# HV_powerSupply_board_20210802.net
KiCad netlist of a schematic drawn in EAGLE
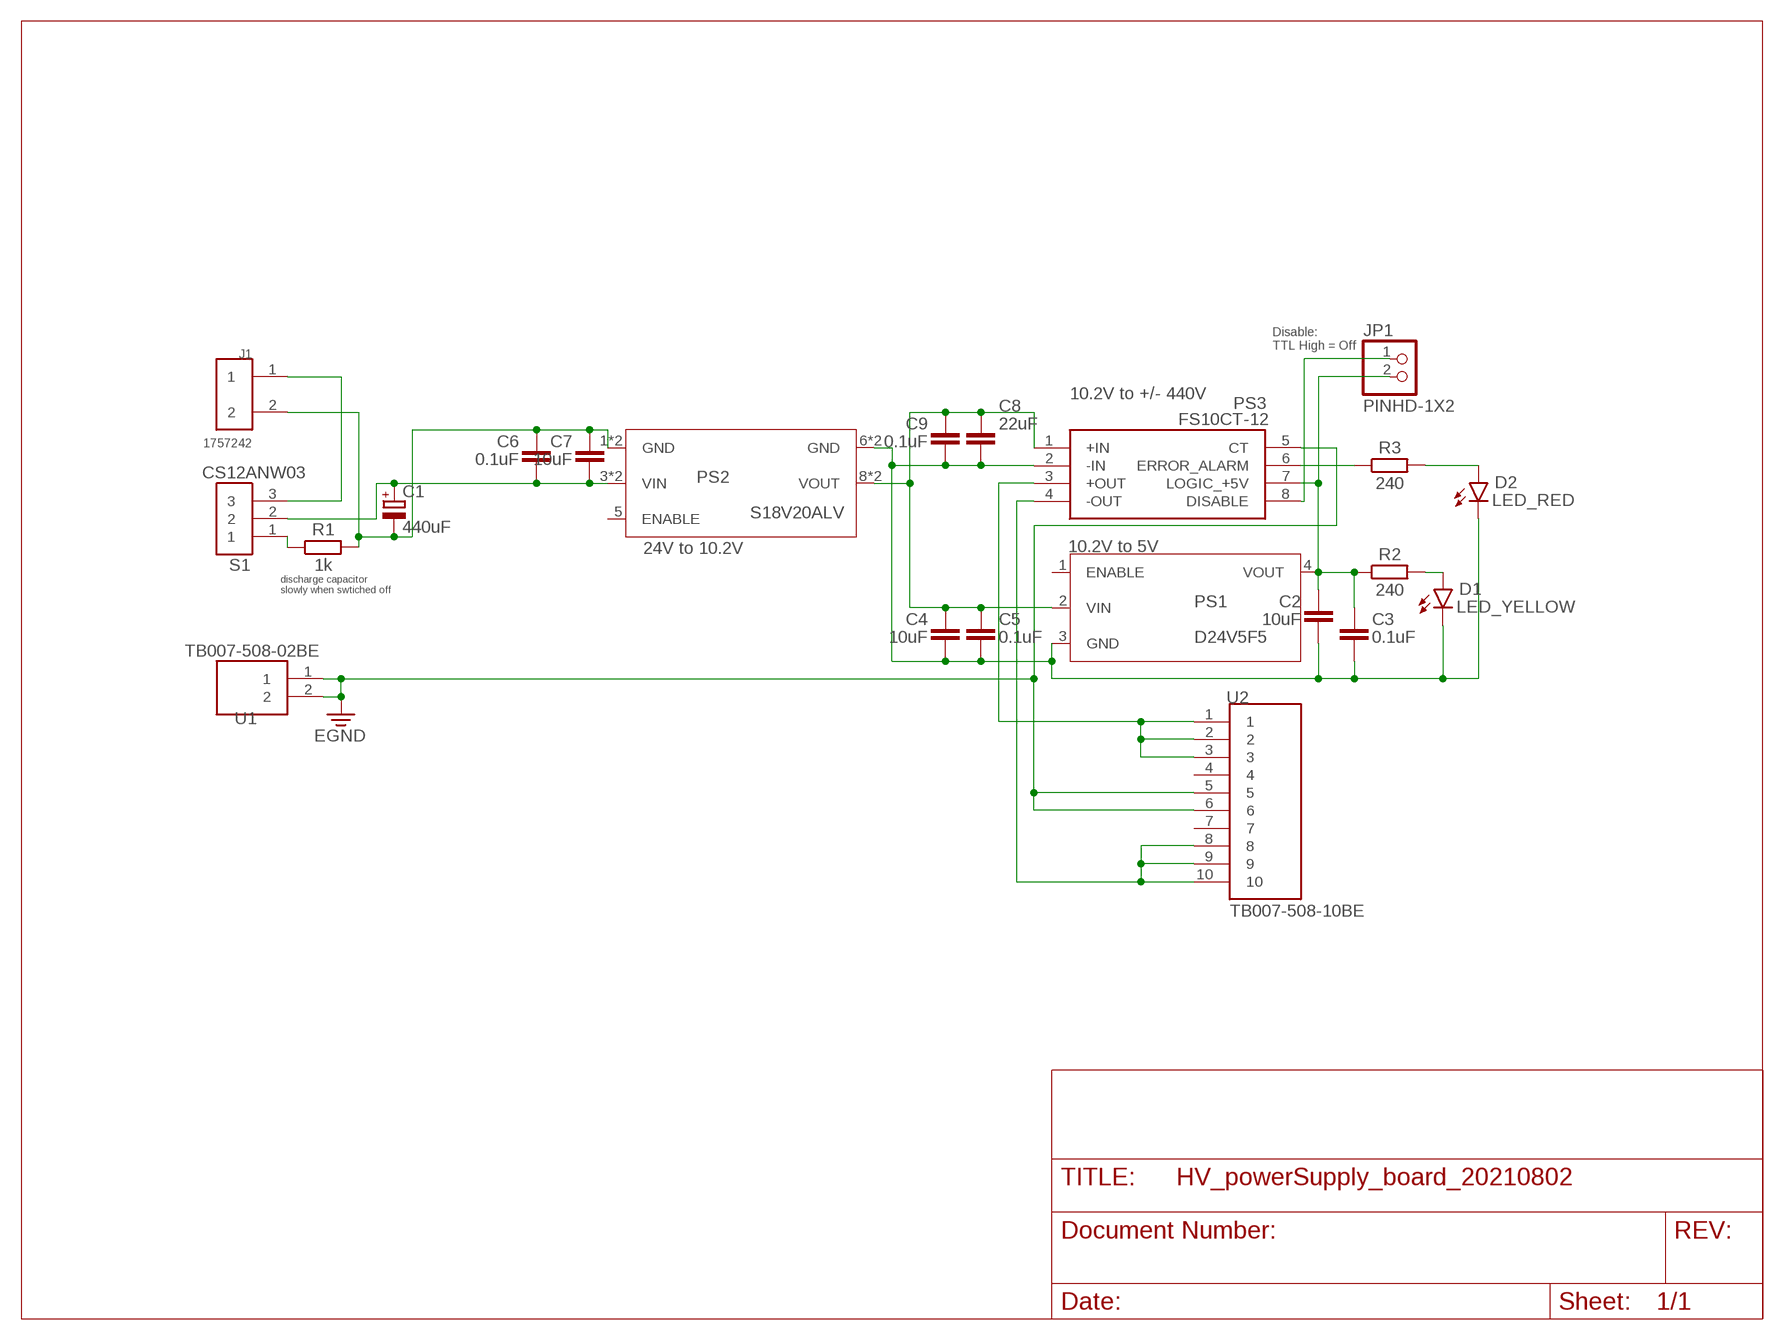
[diagram p0: schematic, sheet 1]

(export (version "E")
  (design (tool "Eeschema 10.0.6"))
  (components
    (comp (ref "C1")
      (value "440uF")
      (footprint "eagle-import:CAPPRD508W65D1000H1100B")
      (libsource (lib "eagle-import") (part "C-POLRADIAL-11MM-DIA_"))
    )
    (comp (ref "C2")
      (value "10uF")
      (footprint "eagle-import:CAPC3225X135")
      (libsource (lib "eagle-import") (part "CCHIP-1210(3225-METRIC)_"))
    )
    (comp (ref "C3")
      (value "0.1uF")
      (footprint "eagle-import:CAPC1608X85")
      (libsource (lib "eagle-import") (part "CCHIP-0603(1608-METRIC)_"))
    )
    (comp (ref "C4")
      (value "10uF")
      (footprint "eagle-import:CAPC3225X135")
      (libsource (lib "eagle-import") (part "CCHIP-1210(3225-METRIC)_"))
    )
    (comp (ref "C5")
      (value "0.1uF")
      (footprint "eagle-import:CAPC1608X85")
      (libsource (lib "eagle-import") (part "CCHIP-0603(1608-METRIC)_"))
    )
    (comp (ref "C6")
      (value "0.1uF")
      (footprint "eagle-import:CAPC1608X85")
      (libsource (lib "eagle-import") (part "CCHIP-0603(1608-METRIC)_"))
    )
    (comp (ref "C7")
      (value "10uF")
      (footprint "eagle-import:CAPC3225X135")
      (libsource (lib "eagle-import") (part "CCHIP-1210(3225-METRIC)_"))
    )
    (comp (ref "C8")
      (value "22uF")
      (footprint "eagle-import:CAPC3225X135")
      (libsource (lib "eagle-import") (part "CCHIP-1210(3225-METRIC)_"))
    )
    (comp (ref "C9")
      (value "0.1uF")
      (footprint "eagle-import:CAPC1608X85")
      (libsource (lib "eagle-import") (part "CCHIP-0603(1608-METRIC)_"))
    )
    (comp (ref "D1")
      (value "LED_YELLOW")
      (footprint "eagle-import:LEDRD254W60D565H860B_Y")
      (libsource (lib "eagle-import") (part "LED_RADIALYELLOW_"))
    )
    (comp (ref "D2")
      (value "LED_RED")
      (footprint "eagle-import:LEDRD254W60D565H860B")
      (libsource (lib "eagle-import") (part "LED_RADIALRED_"))
    )
    (comp (ref "J1")
      (value "1757242")
      (footprint "eagle-import:PHOENIX_1757242")
      (fields (field (name "DIGI-KEY_PART_NUMBER") "277-1106-ND") (field (name "MF") "Phoenix Contact"))
      (libsource (lib "eagle-import") (part "1757242"))
    )
    (comp (ref "JP1")
      (value "PINHD-1X2")
      (footprint "eagle-import:1X02")
      (libsource (lib "eagle-import") (part "PINHD-1X2"))
    )
    (comp (ref "PS1")
      (value "D24V5F5")
      (footprint "eagle-import:D24V5F5")
      (libsource (lib "eagle-import") (part "D24V5F5"))
    )
    (comp (ref "PS2")
      (value "S18V20ALV")
      (footprint "eagle-import:S18V20ALV")
      (libsource (lib "eagle-import") (part "S18V20ALV"))
    )
    (comp (ref "PS3")
      (value "FS10CT-12")
      (footprint "eagle-import:FS10CT12")
      (libsource (lib "eagle-import") (part "FS10CT-12"))
    )
    (comp (ref "R1")
      (value "1k")
      (footprint "eagle-import:RESC3216X70")
      (libsource (lib "eagle-import") (part "RCHIP-1206(3216-METRIC)_"))
    )
    (comp (ref "R2")
      (value "240")
      (footprint "eagle-import:RESC3216X70")
      (libsource (lib "eagle-import") (part "RCHIP-1206(3216-METRIC)_"))
    )
    (comp (ref "R3")
      (value "240")
      (footprint "eagle-import:RESC3216X70")
      (libsource (lib "eagle-import") (part "RCHIP-1206(3216-METRIC)_"))
    )
    (comp (ref "S1")
      (value "CS12ANW03")
      (footprint "eagle-import:CS12ANW03")
      (fields (field (name "MOUSER_PART_NUMBER") "633-CS12ANW03"))
      (libsource (lib "eagle-import") (part "CS12ANW03"))
    )
    (comp (ref "U1")
      (value "TB007-508-02BE")
      (footprint "eagle-import:CUI_TB007-508-02BE")
      (fields (field (name "DIGI-KEY_PART_NUMBER") "102-6203-ND") (field (name "MF") "CUI Devices"))
      (libsource (lib "eagle-import") (part "TB007-508-02BE"))
    )
    (comp (ref "U2")
      (value "TB007-508-10BE")
      (footprint "eagle-import:CUI_TB007-508-10BE")
      (fields (field (name "MANUFACTURER") "CUI"))
      (libsource (lib "eagle-import") (part "TB007-508-10BE"))
    )
  )
  (nets
    (net (code "1") (name "EGND") (class "Default")
      (node (ref "PS3") (pin "5") (pinfunction "CT_5") (pintype "bidirectional"))
      (node (ref "U1") (pin "1") (pinfunction "1_1") (pintype "passive"))
      (node (ref "U1") (pin "2") (pinfunction "2_2") (pintype "passive"))
      (node (ref "U2") (pin "5") (pinfunction "5_5") (pintype "passive"))
      (node (ref "U2") (pin "6") (pinfunction "6_6") (pintype "passive"))
    )
    (net (code "2") (name "Net-(C1-+)") (class "Default")
      (node (ref "C1") (pin "1") (pinfunction "+_1") (pintype "passive"))
      (node (ref "C6") (pin "2") (pinfunction "2_2") (pintype "passive"))
      (node (ref "C7") (pin "2") (pinfunction "2_2") (pintype "passive"))
      (node (ref "PS2") (pin "3") (pinfunction "VIN_3") (pintype "bidirectional"))
      (node (ref "PS2") (pin "4") (pinfunction "VIN_4") (pintype "bidirectional"))
      (node (ref "S1") (pin "2") (pinfunction "2_2") (pintype "bidirectional"))
    )
    (net (code "3") (name "Net-(C1--)") (class "Default")
      (node (ref "C1") (pin "2") (pinfunction "-_2") (pintype "passive"))
      (node (ref "C6") (pin "1") (pinfunction "1_1") (pintype "passive"))
      (node (ref "C7") (pin "1") (pinfunction "1_1") (pintype "passive"))
      (node (ref "J1") (pin "2") (pinfunction "2_2") (pintype "passive"))
      (node (ref "PS2") (pin "1") (pinfunction "GND_1") (pintype "bidirectional"))
      (node (ref "PS2") (pin "2") (pinfunction "GND_2") (pintype "bidirectional"))
      (node (ref "R1") (pin "2") (pinfunction "2_2") (pintype "passive"))
    )
    (net (code "4") (name "Net-(D1-A)") (class "Default")
      (node (ref "D1") (pin "1") (pinfunction "A_1") (pintype "passive"))
      (node (ref "R2") (pin "2") (pinfunction "2_2") (pintype "passive"))
    )
    (net (code "5") (name "Net-(D1-C)") (class "Default")
      (node (ref "C2") (pin "2") (pinfunction "2_2") (pintype "passive"))
      (node (ref "C3") (pin "2") (pinfunction "2_2") (pintype "passive"))
      (node (ref "C4") (pin "2") (pinfunction "2_2") (pintype "passive"))
      (node (ref "C5") (pin "2") (pinfunction "2_2") (pintype "passive"))
      (node (ref "C8") (pin "2") (pinfunction "2_2") (pintype "passive"))
      (node (ref "C9") (pin "2") (pinfunction "2_2") (pintype "passive"))
      (node (ref "D1") (pin "2") (pinfunction "C_2") (pintype "passive"))
      (node (ref "D2") (pin "2") (pinfunction "C_2") (pintype "passive"))
      (node (ref "PS1") (pin "3") (pinfunction "GND_3") (pintype "bidirectional"))
      (node (ref "PS2") (pin "6") (pinfunction "GND_6") (pintype "bidirectional"))
      (node (ref "PS2") (pin "7") (pinfunction "GND_7") (pintype "bidirectional"))
      (node (ref "PS3") (pin "2") (pinfunction "-IN_2") (pintype "bidirectional"))
    )
    (net (code "6") (name "Net-(D2-A)") (class "Default")
      (node (ref "D2") (pin "1") (pinfunction "A_1") (pintype "passive"))
      (node (ref "R3") (pin "2") (pinfunction "2_2") (pintype "passive"))
    )
    (net (code "7") (name "Net-(J1-Pad1)") (class "Default")
      (node (ref "J1") (pin "1") (pinfunction "1_1") (pintype "passive"))
      (node (ref "S1") (pin "3") (pinfunction "3_3") (pintype "bidirectional"))
    )
    (net (code "8") (name "Net-(PS1-VIN)") (class "Default")
      (node (ref "C4") (pin "1") (pinfunction "1_1") (pintype "passive"))
      (node (ref "C5") (pin "1") (pinfunction "1_1") (pintype "passive"))
      (node (ref "C8") (pin "1") (pinfunction "1_1") (pintype "passive"))
      (node (ref "C9") (pin "1") (pinfunction "1_1") (pintype "passive"))
      (node (ref "PS1") (pin "2") (pinfunction "VIN_2") (pintype "bidirectional"))
      (node (ref "PS2") (pin "8") (pinfunction "VOUT_8") (pintype "bidirectional"))
      (node (ref "PS2") (pin "9") (pinfunction "VOUT_9") (pintype "bidirectional"))
      (node (ref "PS3") (pin "1") (pinfunction "+IN_1") (pintype "bidirectional"))
    )
    (net (code "9") (name "Net-(PS1-VOUT)") (class "Default")
      (node (ref "C2") (pin "1") (pinfunction "1_1") (pintype "passive"))
      (node (ref "C3") (pin "1") (pinfunction "1_1") (pintype "passive"))
      (node (ref "JP1") (pin "2") (pinfunction "2_2") (pintype "passive"))
      (node (ref "PS1") (pin "4") (pinfunction "VOUT_4") (pintype "bidirectional"))
      (node (ref "PS3") (pin "7") (pinfunction "LOGIC_+5V_7") (pintype "bidirectional"))
      (node (ref "R2") (pin "1") (pinfunction "1_1") (pintype "passive"))
    )
    (net (code "10") (name "Net-(PS3-+OUT)") (class "Default")
      (node (ref "PS3") (pin "3") (pinfunction "+OUT_3") (pintype "bidirectional"))
      (node (ref "U2") (pin "1") (pinfunction "1_1") (pintype "passive"))
      (node (ref "U2") (pin "2") (pinfunction "2_2") (pintype "passive"))
      (node (ref "U2") (pin "3") (pinfunction "3_3") (pintype "passive"))
    )
    (net (code "11") (name "Net-(PS3--OUT)") (class "Default")
      (node (ref "PS3") (pin "4") (pinfunction "-OUT_4") (pintype "bidirectional"))
      (node (ref "U2") (pin "10") (pinfunction "10_10") (pintype "passive"))
      (node (ref "U2") (pin "8") (pinfunction "8_8") (pintype "passive"))
      (node (ref "U2") (pin "9") (pinfunction "9_9") (pintype "passive"))
    )
    (net (code "12") (name "Net-(PS3-DISABLE)") (class "Default")
      (node (ref "JP1") (pin "1") (pinfunction "1_1") (pintype "passive"))
      (node (ref "PS3") (pin "8") (pinfunction "DISABLE_8") (pintype "bidirectional"))
    )
    (net (code "13") (name "Net-(PS3-ERROR_ALARM)") (class "Default")
      (node (ref "PS3") (pin "6") (pinfunction "ERROR_ALARM_6") (pintype "bidirectional"))
      (node (ref "R3") (pin "1") (pinfunction "1_1") (pintype "passive"))
    )
    (net (code "14") (name "Net-(R1-Pad1)") (class "Default")
      (node (ref "R1") (pin "1") (pinfunction "1_1") (pintype "passive"))
      (node (ref "S1") (pin "1") (pinfunction "1_1") (pintype "bidirectional"))
    )
    (net (code "15") (name "unconnected-(PS1-ENABLE-Pad1)") (class "Default")
      (node (ref "PS1") (pin "1") (pinfunction "ENABLE_1") (pintype "bidirectional"))
    )
    (net (code "16") (name "unconnected-(PS2-ENABLE-Pad5)") (class "Default")
      (node (ref "PS2") (pin "5") (pinfunction "ENABLE_5") (pintype "bidirectional"))
    )
    (net (code "17") (name "unconnected-(U2-Pad4)") (class "Default")
      (node (ref "U2") (pin "4") (pinfunction "4_4") (pintype "passive"))
    )
    (net (code "18") (name "unconnected-(U2-Pad7)") (class "Default")
      (node (ref "U2") (pin "7") (pinfunction "7_7") (pintype "passive"))
    )
  )
)
